# 04_Brushed_Motor_ICs.net
KiCad netlist of a schematic drawn in Altium Designer
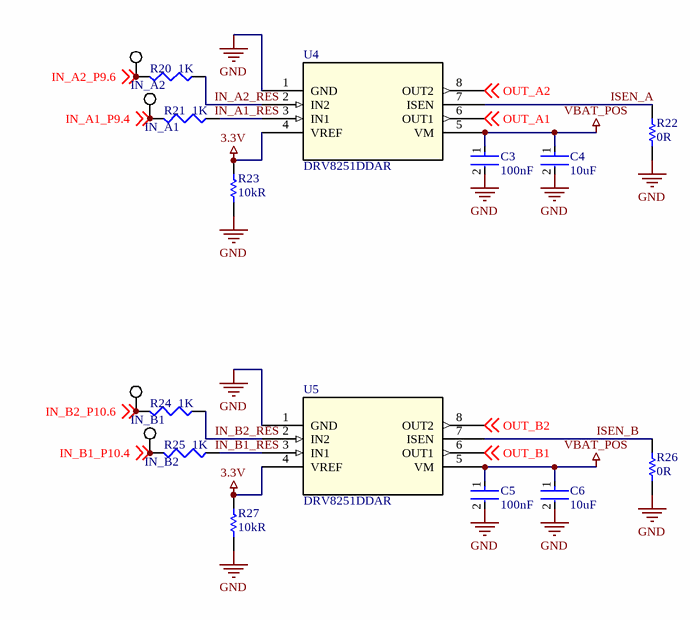
[diagram p0: 04_Brushed_Motor_ICs.SchDoc]

(export (version "E")
  (design (tool "Eeschema 10.0.6"))
  (components
    (comp (ref "C3")
      (value "100nF")
      (footprint "CAP_0805")
      (description "CAP CER 0.1UF 50V X7R 0805")
      (fields
        (field (name "MANUFACTURER") "KEMET")
        (field (name "MANUFACTURER PART NUMBER") "C0805C104K5RACTU")
      )
      (libsource (lib "ECE453") (part "CMP-2007-00279-2"))
    )
    (comp (ref "C4")
      (value "10uF")
      (footprint "CAP_0805")
      (description "CAP CER 10UF 10V X5R 0805")
      (fields
        (field (name "MANUFACTURER") "KEMET")
        (field (name "MANUFACTURER PART NUMBER") "C0805C106K8PACTU")
      )
      (libsource (lib "ECE453") (part "CMP-2007-03243-2"))
    )
    (comp (ref "C5")
      (value "100nF")
      (footprint "CAP_0805")
      (description "CAP CER 0.1UF 50V X7R 0805")
      (fields
        (field (name "MANUFACTURER") "KEMET")
        (field (name "MANUFACTURER PART NUMBER") "C0805C104K5RACTU")
      )
      (libsource (lib "ECE453") (part "CMP-2007-00279-2"))
    )
    (comp (ref "C6")
      (value "10uF")
      (footprint "CAP_0805")
      (description "CAP CER 10UF 10V X5R 0805")
      (fields
        (field (name "MANUFACTURER") "KEMET")
        (field (name "MANUFACTURER PART NUMBER") "C0805C106K8PACTU")
      )
      (libsource (lib "ECE453") (part "CMP-2007-03243-2"))
    )
    (comp (ref "IN_A1")
      (value "5019")
      (footprint "KSTN-5019_V")
      (description "Test Point, 1 Position SMD, RoHS, Tape and Reel")
      (fields (field (name "MANUFACTURER") "Keystone Electronics"))
      (libsource (lib "ECE453") (part "CMP-1672-00008-1"))
    )
    (comp (ref "IN_A2")
      (value "5019")
      (footprint "KSTN-5019_V")
      (description "Test Point, 1 Position SMD, RoHS, Tape and Reel")
      (fields (field (name "MANUFACTURER") "Keystone Electronics"))
      (libsource (lib "ECE453") (part "CMP-1672-00008-1"))
    )
    (comp (ref "IN_B1")
      (value "5019")
      (footprint "KSTN-5019_V")
      (description "Test Point, 1 Position SMD, RoHS, Tape and Reel")
      (fields (field (name "MANUFACTURER") "Keystone Electronics"))
      (libsource (lib "ECE453") (part "CMP-1672-00008-1"))
    )
    (comp (ref "IN_B2")
      (value "5019")
      (footprint "KSTN-5019_V")
      (description "Test Point, 1 Position SMD, RoHS, Tape and Reel")
      (fields (field (name "MANUFACTURER") "Keystone Electronics"))
      (libsource (lib "ECE453") (part "CMP-1672-00008-1"))
    )
    (comp (ref "R20")
      (value "1K")
      (footprint "RESC2013X70X40ML20T20")
      (description "Res Thick Film 0805 1K Ohm 1% 0.125W(1/8W) ±100ppm/C Pad SMD Automotive T/R")
      (fields
        (field (name "MANUFACTURER") "Stackpole Electronics")
        (field (name "MANUFACTURER PART NUMBER") "RMCF0805FT1K00")
      )
      (libsource (lib "ECE453") (part "Res3_1"))
    )
    (comp (ref "R21")
      (value "1K")
      (footprint "RESC2013X70X40ML20T20")
      (description "Res Thick Film 0805 1K Ohm 1% 0.125W(1/8W) ±100ppm/C Pad SMD Automotive T/R")
      (fields
        (field (name "MANUFACTURER") "Stackpole Electronics")
        (field (name "MANUFACTURER PART NUMBER") "RMCF0805FT1K00")
      )
      (libsource (lib "ECE453") (part "Res3_1"))
    )
    (comp (ref "R22")
      (value "0R")
      (footprint "RESC2013X70X40NL20T20")
      (description "Chip Resistor, 0 Ohm, +/- 1%, 0.125 W, -55 to 155 degC, 0805 (2012 Metric), RoHS, Tape and Reel")
      (fields (field (name "PARTNUMBER") "ERJ-6GEY0R00V") (field (name "TOLERANCE") "5%"))
      (libsource (lib "ECE453") (part "CMP-1665-00002-5"))
    )
    (comp (ref "R23")
      (value "RC0805FR-0710KL")
      (footprint "RESC2013X60X35NL10T20")
      (description "Chip Resistor, 10 KOhm, +/- 1%, 0.125 W, -55 to 155 degC, 0805 (2012 Metric), RoHS, Tape and Reel")
      (fields
        (field (name "MANUFACTURER") "Yageo")
        (field (name "TOLERANCE") "1%")
        (field (name "RESISTANCE") "10kR")
      )
      (libsource (lib "ECE453") (part "CMP-1659-00013-4"))
    )
    (comp (ref "R24")
      (value "1K")
      (footprint "RESC2013X70X40ML20T20")
      (description "Res Thick Film 0805 1K Ohm 1% 0.125W(1/8W) ±100ppm/C Pad SMD Automotive T/R")
      (fields
        (field (name "MANUFACTURER") "Stackpole Electronics")
        (field (name "MANUFACTURER PART NUMBER") "RMCF0805FT1K00")
      )
      (libsource (lib "ECE453") (part "Res3_1"))
    )
    (comp (ref "R25")
      (value "1K")
      (footprint "RESC2013X70X40ML20T20")
      (description "Res Thick Film 0805 1K Ohm 1% 0.125W(1/8W) ±100ppm/C Pad SMD Automotive T/R")
      (fields
        (field (name "MANUFACTURER") "Stackpole Electronics")
        (field (name "MANUFACTURER PART NUMBER") "RMCF0805FT1K00")
      )
      (libsource (lib "ECE453") (part "Res3_1"))
    )
    (comp (ref "R26")
      (value "0R")
      (footprint "RESC2013X70X40NL20T20")
      (description "Chip Resistor, 0 Ohm, +/- 1%, 0.125 W, -55 to 155 degC, 0805 (2012 Metric), RoHS, Tape and Reel")
      (fields (field (name "PARTNUMBER") "ERJ-6GEY0R00V") (field (name "TOLERANCE") "5%"))
      (libsource (lib "ECE453") (part "CMP-1665-00002-5"))
    )
    (comp (ref "R27")
      (value "RC0805FR-0710KL")
      (footprint "RESC2013X60X35NL10T20")
      (description "Chip Resistor, 10 KOhm, +/- 1%, 0.125 W, -55 to 155 degC, 0805 (2012 Metric), RoHS, Tape and Reel")
      (fields
        (field (name "MANUFACTURER") "Yageo")
        (field (name "TOLERANCE") "1%")
        (field (name "RESISTANCE") "10kR")
      )
      (libsource (lib "ECE453") (part "CMP-1659-00013-4"))
    )
    (comp (ref "U4")
      (value "DRV8251DDAR")
      (footprint "POWERPAD_DDA_TEX-M")
      (description "No Description Available")
      (fields (field (name "COPYRIGHT") "Copyright (C) 2023 Ultra Librarian. All rights reserved."))
      (libsource (lib "DRV8251DDAR") (part "DRV8251DDAR"))
    )
    (comp (ref "U5")
      (value "DRV8251DDAR")
      (footprint "POWERPAD_DDA_TEX-M")
      (description "No Description Available")
      (fields (field (name "COPYRIGHT") "Copyright (C) 2023 Ultra Librarian. All rights reserved."))
      (libsource (lib "DRV8251DDAR") (part "DRV8251DDAR"))
    )
  )
  (nets
    (net (code "1") (name "/IN_A1_RES") (class "Default")
      (node (ref "R21") (pin "1") (pinfunction "1_1") (pintype "passive"))
      (node (ref "U4") (pin "3") (pinfunction "IN1_3") (pintype "input"))
    )
    (net (code "2") (name "/IN_A2_RES") (class "Default")
      (node (ref "R20") (pin "1") (pinfunction "1_1") (pintype "passive"))
      (node (ref "U4") (pin "2") (pinfunction "IN2_2") (pintype "input"))
    )
    (net (code "3") (name "/IN_B1_RES") (class "Default")
      (node (ref "R25") (pin "1") (pinfunction "1_1") (pintype "passive"))
      (node (ref "U5") (pin "3") (pinfunction "IN1_3") (pintype "input"))
    )
    (net (code "4") (name "/IN_B2_RES") (class "Default")
      (node (ref "R24") (pin "1") (pinfunction "1_1") (pintype "passive"))
      (node (ref "U5") (pin "2") (pinfunction "IN2_2") (pintype "input"))
    )
    (net (code "5") (name "/ISEN_A") (class "Default")
      (node (ref "R22") (pin "2") (pinfunction "2_2") (pintype "passive"))
      (node (ref "U4") (pin "7") (pinfunction "ISEN_7") (pintype "power_in"))
    )
    (net (code "6") (name "/ISEN_B") (class "Default")
      (node (ref "R26") (pin "2") (pinfunction "2_2") (pintype "passive"))
      (node (ref "U5") (pin "7") (pinfunction "ISEN_7") (pintype "power_in"))
    )
    (net (code "7") (name "3.3V") (class "Default")
      (node (ref "R23") (pin "2") (pinfunction "2_2") (pintype "passive"))
      (node (ref "R27") (pin "2") (pinfunction "2_2") (pintype "passive"))
      (node (ref "U4") (pin "4") (pinfunction "VREF_4") (pintype "power_in"))
      (node (ref "U5") (pin "4") (pinfunction "VREF_4") (pintype "power_in"))
    )
    (net (code "8") (name "GND") (class "Default")
      (node (ref "C3") (pin "2") (pinfunction "2_2") (pintype "passive"))
      (node (ref "C4") (pin "2") (pinfunction "2_2") (pintype "passive"))
      (node (ref "C5") (pin "2") (pinfunction "2_2") (pintype "passive"))
      (node (ref "C6") (pin "2") (pinfunction "2_2") (pintype "passive"))
      (node (ref "R22") (pin "1") (pinfunction "1_1") (pintype "passive"))
      (node (ref "R23") (pin "1") (pinfunction "1_1") (pintype "passive"))
      (node (ref "R26") (pin "1") (pinfunction "1_1") (pintype "passive"))
      (node (ref "R27") (pin "1") (pinfunction "1_1") (pintype "passive"))
      (node (ref "U4") (pin "1") (pinfunction "GND_1") (pintype "power_in"))
      (node (ref "U5") (pin "1") (pinfunction "GND_1") (pintype "power_in"))
    )
    (net (code "9") (name "IN_A1_P9.4") (class "Default")
      (node (ref "IN_A1") (pin "1") (pinfunction "1_1") (pintype "passive"))
      (node (ref "R21") (pin "2") (pinfunction "2_2") (pintype "passive"))
    )
    (net (code "10") (name "IN_A2_P9.6") (class "Default")
      (node (ref "IN_A2") (pin "1") (pinfunction "1_1") (pintype "passive"))
      (node (ref "R20") (pin "2") (pinfunction "2_2") (pintype "passive"))
    )
    (net (code "11") (name "IN_B1_P10.4") (class "Default")
      (node (ref "IN_B2") (pin "1") (pinfunction "1_1") (pintype "passive"))
      (node (ref "R25") (pin "2") (pinfunction "2_2") (pintype "passive"))
    )
    (net (code "12") (name "IN_B2_P10.6") (class "Default")
      (node (ref "IN_B1") (pin "1") (pinfunction "1_1") (pintype "passive"))
      (node (ref "R24") (pin "2") (pinfunction "2_2") (pintype "passive"))
    )
    (net (code "13") (name "OUT_A1") (class "Default")
      (node (ref "U4") (pin "6") (pinfunction "OUT1_6") (pintype "output"))
    )
    (net (code "14") (name "OUT_A2") (class "Default")
      (node (ref "U4") (pin "8") (pinfunction "OUT2_8") (pintype "output"))
    )
    (net (code "15") (name "OUT_B1") (class "Default")
      (node (ref "U5") (pin "6") (pinfunction "OUT1_6") (pintype "output"))
    )
    (net (code "16") (name "OUT_B2") (class "Default")
      (node (ref "U5") (pin "8") (pinfunction "OUT2_8") (pintype "output"))
    )
    (net (code "17") (name "VBAT_POS") (class "Default")
      (node (ref "C3") (pin "1") (pinfunction "1_1") (pintype "passive"))
      (node (ref "C4") (pin "1") (pinfunction "1_1") (pintype "passive"))
      (node (ref "C5") (pin "1") (pinfunction "1_1") (pintype "passive"))
      (node (ref "C6") (pin "1") (pinfunction "1_1") (pintype "passive"))
      (node (ref "U4") (pin "5") (pinfunction "VM_5") (pintype "power_in"))
      (node (ref "U5") (pin "5") (pinfunction "VM_5") (pintype "power_in"))
    )
  )
)
